# supply.net
KiCad netlist of a schematic drawn in EAGLE
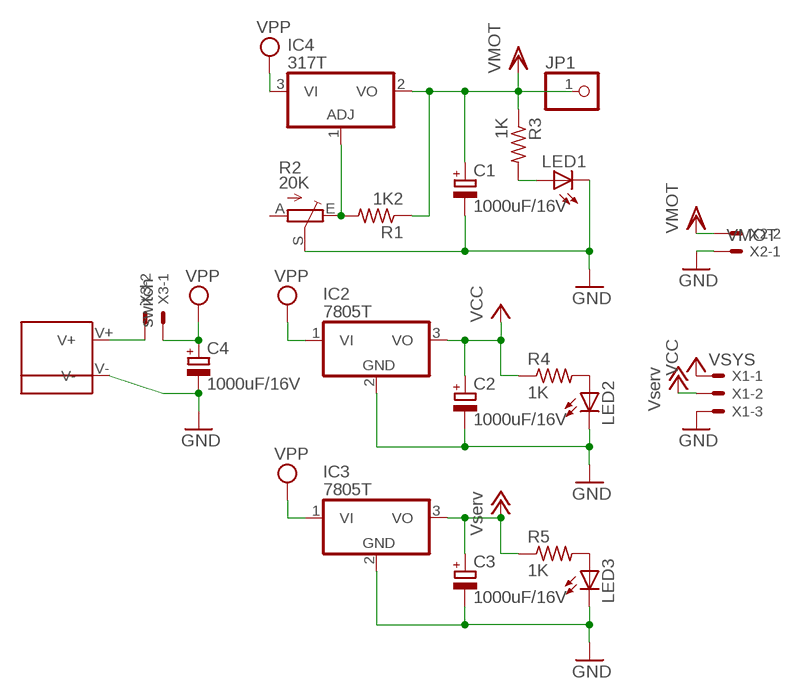
[diagram p0: schematic, sheet 1]

(export (version "E")
  (design (tool "Eeschema 10.0.6"))
  (components
    (comp (ref "C1")
      (value "1000uF/16V")
      (footprint "eagle-import:E3,5-10")
      (libsource (lib "eagle-import") (part "CPOL-EUE3.5-10"))
    )
    (comp (ref "C2")
      (value "1000uF/16V")
      (footprint "eagle-import:E3,5-10")
      (libsource (lib "eagle-import") (part "CPOL-EUE3.5-10"))
    )
    (comp (ref "C3")
      (value "1000uF/16V")
      (footprint "eagle-import:E3,5-10")
      (libsource (lib "eagle-import") (part "CPOL-EUE3.5-10"))
    )
    (comp (ref "C4")
      (value "1000uF/16V")
      (footprint "eagle-import:E3,5-10")
      (libsource (lib "eagle-import") (part "CPOL-EUE3.5-10"))
    )
    (comp (ref "IC2")
      (value "7805T")
      (footprint "eagle-import:TO220H")
      (libsource (lib "eagle-import") (part "78T05"))
    )
    (comp (ref "IC3")
      (value "7805T")
      (footprint "eagle-import:TO220H")
      (libsource (lib "eagle-import") (part "78T05"))
    )
    (comp (ref "IC4")
      (value "317T")
      (footprint "eagle-import:TO220H")
      (libsource (lib "eagle-import") (part "317T"))
    )
    (comp (ref "JP1")
      (value "PINHD-1X1")
      (footprint "eagle-import:1X01")
      (libsource (lib "eagle-import") (part "PINHD-1X1"))
    )
    (comp (ref "LED1")
      (value "LED3MM")
      (footprint "eagle-import:LED3MM")
      (libsource (lib "eagle-import") (part "LED3MM"))
    )
    (comp (ref "LED2")
      (value "LED3MM")
      (footprint "eagle-import:LED3MM")
      (libsource (lib "eagle-import") (part "LED3MM"))
    )
    (comp (ref "LED3")
      (value "LED3MM")
      (footprint "eagle-import:LED3MM")
      (libsource (lib "eagle-import") (part "LED3MM"))
    )
    (comp (ref "R1")
      (value "1K2")
      (footprint "eagle-import:0207_10")
      (libsource (lib "eagle-import") (part "R-US_0207/10"))
    )
    (comp (ref "R2")
      (value "20K")
      (footprint "eagle-import:CA6V")
      (libsource (lib "eagle-import") (part "TRIM_EU-CA6V"))
    )
    (comp (ref "R3")
      (value "1K")
      (footprint "eagle-import:0207_10")
      (libsource (lib "eagle-import") (part "R-US_0207/10"))
    )
    (comp (ref "R4")
      (value "1K")
      (footprint "eagle-import:0207_10")
      (libsource (lib "eagle-import") (part "R-US_0207/10"))
    )
    (comp (ref "R5")
      (value "1K")
      (footprint "eagle-import:0207_10")
      (libsource (lib "eagle-import") (part "R-US_0207/10"))
    )
    (comp (ref "VIN")
      (value "CON-XT60M")
      (footprint "eagle-import:CON-XT60M")
      (libsource (lib "eagle-import") (part "CON-XT60M"))
    )
    (comp (ref "X1")
      (value "VSYS")
      (footprint "eagle-import:22-23-2031")
      (fields (field (name "MF") "MOLEX") (field (name "MPN") "22-23-2031"))
      (libsource (lib "eagle-import") (part "22-23-2031"))
    )
    (comp (ref "X2")
      (value "VMOT")
      (footprint "eagle-import:22-23-2021")
      (fields (field (name "MF") "MOLEX") (field (name "MPN") "22-23-2021"))
      (libsource (lib "eagle-import") (part "22-23-2021"))
    )
    (comp (ref "X3")
      (value "switch")
      (footprint "eagle-import:22-23-2021")
      (fields
        (field (name "MF") "MOLEX")
        (field (name "MPN") "22-23-2021")
        (field (name "MF_1") "MOLEX")
        (field (name "MPN_1") "22-23-2021")
        (field (name "OC_FARNELL") "1462926")
        (field (name "OC_NEWARK") "25C3832")
      )
      (libsource (lib "eagle-import") (part "22-23-2021"))
    )
  )
  (nets
    (net (code "1") (name "GND") (class "Default")
      (node (ref "C1") (pin "-") (pinfunction "-_-") (pintype "passive"))
      (node (ref "C2") (pin "-") (pinfunction "-_-") (pintype "passive"))
      (node (ref "C3") (pin "-") (pinfunction "-_-") (pintype "passive"))
      (node (ref "C4") (pin "-") (pinfunction "-_-") (pintype "passive"))
      (node (ref "IC2") (pin "2") (pinfunction "GND_2") (pintype "passive"))
      (node (ref "IC3") (pin "2") (pinfunction "GND_2") (pintype "passive"))
      (node (ref "LED1") (pin "K") (pinfunction "C_K") (pintype "passive"))
      (node (ref "LED2") (pin "K") (pinfunction "C_K") (pintype "passive"))
      (node (ref "LED3") (pin "K") (pinfunction "C_K") (pintype "passive"))
      (node (ref "R2") (pin "S") (pinfunction "S_S") (pintype "passive"))
      (node (ref "VIN") (pin "V-") (pinfunction "V-_V-") (pintype "power_in"))
      (node (ref "X1") (pin "3") (pinfunction "S_3") (pintype "passive"))
      (node (ref "X2") (pin "1") (pinfunction "S_1") (pintype "passive"))
    )
    (net (code "2") (name "Net-(IC4-ADJ)") (class "Default")
      (node (ref "IC4") (pin "1") (pinfunction "ADJ_1") (pintype "input"))
      (node (ref "R1") (pin "2") (pinfunction "2_2") (pintype "passive"))
      (node (ref "R2") (pin "E") (pinfunction "E_E") (pintype "passive"))
    )
    (net (code "3") (name "Net-(LED1-PadA)") (class "Default")
      (node (ref "LED1") (pin "A") (pinfunction "A_A") (pintype "passive"))
      (node (ref "R3") (pin "2") (pinfunction "2_2") (pintype "passive"))
    )
    (net (code "4") (name "Net-(LED2-PadA)") (class "Default")
      (node (ref "LED2") (pin "A") (pinfunction "A_A") (pintype "passive"))
      (node (ref "R4") (pin "2") (pinfunction "2_2") (pintype "passive"))
    )
    (net (code "5") (name "Net-(LED3-PadA)") (class "Default")
      (node (ref "LED3") (pin "A") (pinfunction "A_A") (pintype "passive"))
      (node (ref "R5") (pin "2") (pinfunction "2_2") (pintype "passive"))
    )
    (net (code "6") (name "Net-(X3B-S)") (class "Default")
      (node (ref "VIN") (pin "V+") (pinfunction "V+_V+") (pintype "power_in"))
      (node (ref "X3") (pin "2") (pinfunction "S_2") (pintype "passive"))
    )
    (net (code "7") (name "VCC") (class "Default")
      (node (ref "C2") (pin "+") (pinfunction "+_+") (pintype "passive"))
      (node (ref "IC2") (pin "3") (pinfunction "VO_3") (pintype "passive"))
      (node (ref "R4") (pin "1") (pinfunction "1_1") (pintype "passive"))
      (node (ref "X1") (pin "1") (pinfunction "S_1") (pintype "passive"))
    )
    (net (code "8") (name "VMOT") (class "Default")
      (node (ref "C1") (pin "+") (pinfunction "+_+") (pintype "passive"))
      (node (ref "IC4") (pin "2") (pinfunction "VO_2") (pintype "passive"))
      (node (ref "JP1") (pin "1") (pinfunction "1_1") (pintype "passive"))
      (node (ref "R1") (pin "1") (pinfunction "1_1") (pintype "passive"))
      (node (ref "R3") (pin "1") (pinfunction "1_1") (pintype "passive"))
      (node (ref "X2") (pin "2") (pinfunction "S_2") (pintype "passive"))
    )
    (net (code "9") (name "VPP") (class "Default")
      (node (ref "C4") (pin "+") (pinfunction "+_+") (pintype "passive"))
      (node (ref "IC2") (pin "1") (pinfunction "VI_1") (pintype "input"))
      (node (ref "IC3") (pin "1") (pinfunction "VI_1") (pintype "input"))
      (node (ref "IC4") (pin "3") (pinfunction "VI_3") (pintype "input"))
      (node (ref "X3") (pin "1") (pinfunction "S_1") (pintype "passive"))
    )
    (net (code "10") (name "Vserv") (class "Default")
      (node (ref "C3") (pin "+") (pinfunction "+_+") (pintype "passive"))
      (node (ref "IC3") (pin "3") (pinfunction "VO_3") (pintype "passive"))
      (node (ref "R5") (pin "1") (pinfunction "1_1") (pintype "passive"))
      (node (ref "X1") (pin "2") (pinfunction "S_2") (pintype "passive"))
    )
    (net (code "11") (name "unconnected-(R2-PadA)") (class "Default")
      (node (ref "R2") (pin "A") (pinfunction "A_A") (pintype "passive"))
    )
  )
)
